# Schaltplan.net
KiCad netlist of a schematic drawn in EAGLE
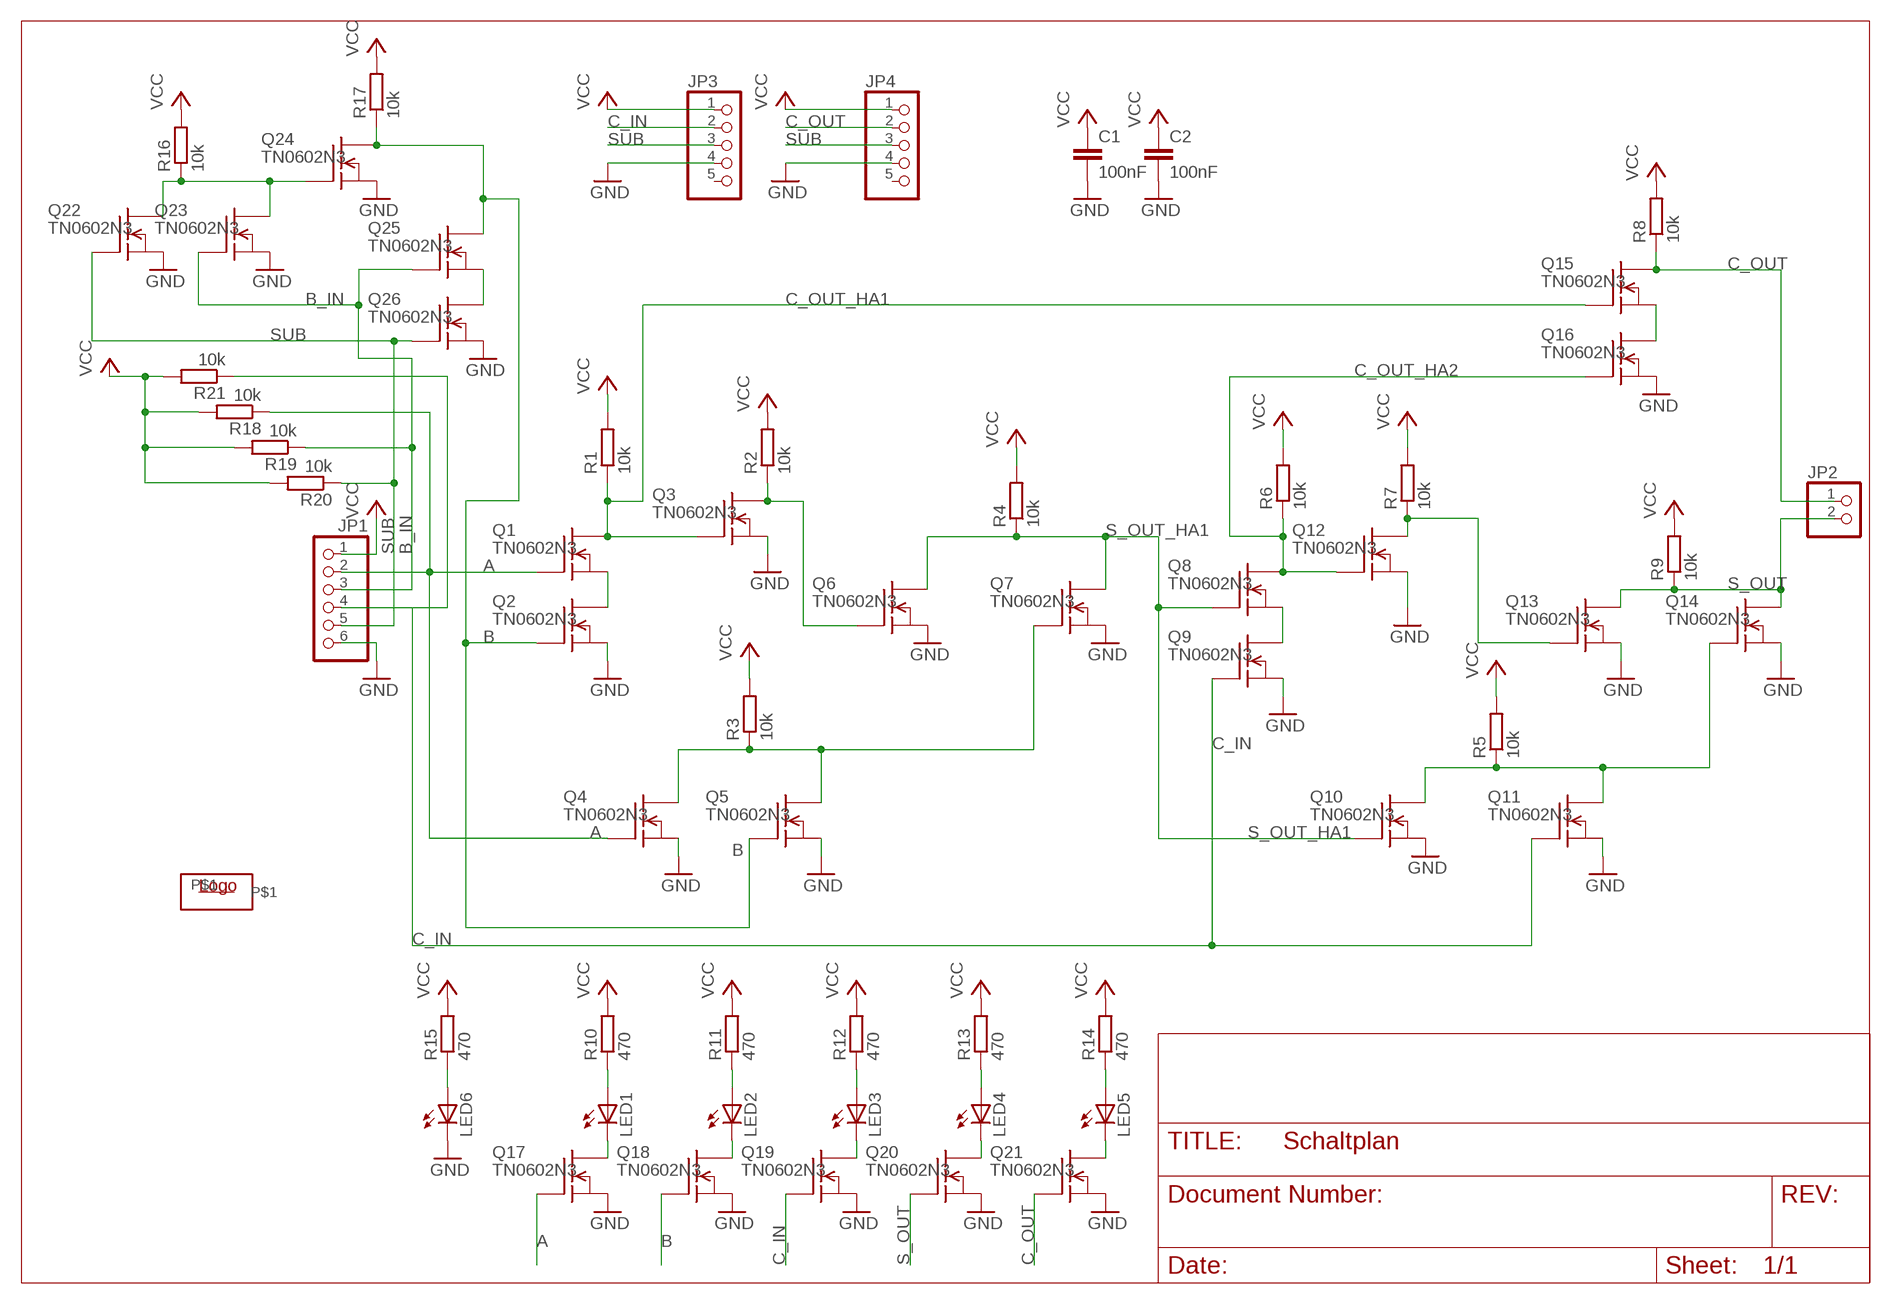
[diagram p0: schematic, sheet 1]

(export (version "E")
  (design (tool "Eeschema 10.0.6"))
  (components
    (comp (ref "C1")
      (value "100nF")
      (footprint "eagle-import:C025-024X044")
      (libsource (lib "eagle-import") (part "C-EU025-024X044"))
    )
    (comp (ref "C2")
      (value "100nF")
      (footprint "eagle-import:C025-024X044")
      (libsource (lib "eagle-import") (part "C-EU025-024X044"))
    )
    (comp (ref "JP1")
      (value "PINHD-1X6")
      (footprint "eagle-import:1X06")
      (libsource (lib "eagle-import") (part "PINHD-1X6"))
    )
    (comp (ref "JP2")
      (value "PINHD-1X2")
      (footprint "eagle-import:1X02")
      (libsource (lib "eagle-import") (part "PINHD-1X2"))
    )
    (comp (ref "JP3")
      (value "PINHD-1X5")
      (footprint "eagle-import:1X05")
      (libsource (lib "eagle-import") (part "PINHD-1X5"))
    )
    (comp (ref "JP4")
      (value "PINHD-1X5")
      (footprint "eagle-import:1X05")
      (libsource (lib "eagle-import") (part "PINHD-1X5"))
    )
    (comp (ref "LED1")
      (value "LED3MM")
      (footprint "eagle-import:LED3MM")
      (libsource (lib "eagle-import") (part "LED3MM"))
    )
    (comp (ref "LED2")
      (value "LED3MM")
      (footprint "eagle-import:LED3MM")
      (libsource (lib "eagle-import") (part "LED3MM"))
    )
    (comp (ref "LED3")
      (value "LED3MM")
      (footprint "eagle-import:LED3MM")
      (libsource (lib "eagle-import") (part "LED3MM"))
    )
    (comp (ref "LED4")
      (value "LED3MM")
      (footprint "eagle-import:LED3MM")
      (libsource (lib "eagle-import") (part "LED3MM"))
    )
    (comp (ref "LED5")
      (value "LED3MM")
      (footprint "eagle-import:LED3MM")
      (libsource (lib "eagle-import") (part "LED3MM"))
    )
    (comp (ref "LED6")
      (value "LED3MM")
      (footprint "eagle-import:LED3MM")
      (libsource (lib "eagle-import") (part "LED3MM"))
    )
    (comp (ref "Q1")
      (value "TN0602N3")
      (footprint "eagle-import:TO-92")
      (libsource (lib "eagle-import") (part "TN0602N3"))
    )
    (comp (ref "Q2")
      (value "TN0602N3")
      (footprint "eagle-import:TO-92")
      (libsource (lib "eagle-import") (part "TN0602N3"))
    )
    (comp (ref "Q3")
      (value "TN0602N3")
      (footprint "eagle-import:TO-92")
      (libsource (lib "eagle-import") (part "TN0602N3"))
    )
    (comp (ref "Q4")
      (value "TN0602N3")
      (footprint "eagle-import:TO-92")
      (libsource (lib "eagle-import") (part "TN0602N3"))
    )
    (comp (ref "Q5")
      (value "TN0602N3")
      (footprint "eagle-import:TO-92")
      (libsource (lib "eagle-import") (part "TN0602N3"))
    )
    (comp (ref "Q6")
      (value "TN0602N3")
      (footprint "eagle-import:TO-92")
      (libsource (lib "eagle-import") (part "TN0602N3"))
    )
    (comp (ref "Q7")
      (value "TN0602N3")
      (footprint "eagle-import:TO-92")
      (libsource (lib "eagle-import") (part "TN0602N3"))
    )
    (comp (ref "Q8")
      (value "TN0602N3")
      (footprint "eagle-import:TO-92")
      (libsource (lib "eagle-import") (part "TN0602N3"))
    )
    (comp (ref "Q9")
      (value "TN0602N3")
      (footprint "eagle-import:TO-92")
      (libsource (lib "eagle-import") (part "TN0602N3"))
    )
    (comp (ref "Q10")
      (value "TN0602N3")
      (footprint "eagle-import:TO-92")
      (libsource (lib "eagle-import") (part "TN0602N3"))
    )
    (comp (ref "Q11")
      (value "TN0602N3")
      (footprint "eagle-import:TO-92")
      (libsource (lib "eagle-import") (part "TN0602N3"))
    )
    (comp (ref "Q12")
      (value "TN0602N3")
      (footprint "eagle-import:TO-92")
      (libsource (lib "eagle-import") (part "TN0602N3"))
    )
    (comp (ref "Q13")
      (value "TN0602N3")
      (footprint "eagle-import:TO-92")
      (libsource (lib "eagle-import") (part "TN0602N3"))
    )
    (comp (ref "Q14")
      (value "TN0602N3")
      (footprint "eagle-import:TO-92")
      (libsource (lib "eagle-import") (part "TN0602N3"))
    )
    (comp (ref "Q15")
      (value "TN0602N3")
      (footprint "eagle-import:TO-92")
      (libsource (lib "eagle-import") (part "TN0602N3"))
    )
    (comp (ref "Q16")
      (value "TN0602N3")
      (footprint "eagle-import:TO-92")
      (libsource (lib "eagle-import") (part "TN0602N3"))
    )
    (comp (ref "Q17")
      (value "TN0602N3")
      (footprint "eagle-import:TO-92")
      (libsource (lib "eagle-import") (part "TN0602N3"))
    )
    (comp (ref "Q18")
      (value "TN0602N3")
      (footprint "eagle-import:TO-92")
      (libsource (lib "eagle-import") (part "TN0602N3"))
    )
    (comp (ref "Q19")
      (value "TN0602N3")
      (footprint "eagle-import:TO-92")
      (libsource (lib "eagle-import") (part "TN0602N3"))
    )
    (comp (ref "Q20")
      (value "TN0602N3")
      (footprint "eagle-import:TO-92")
      (libsource (lib "eagle-import") (part "TN0602N3"))
    )
    (comp (ref "Q21")
      (value "TN0602N3")
      (footprint "eagle-import:TO-92")
      (libsource (lib "eagle-import") (part "TN0602N3"))
    )
    (comp (ref "Q22")
      (value "TN0602N3")
      (footprint "eagle-import:TO-92")
      (libsource (lib "eagle-import") (part "TN0602N3"))
    )
    (comp (ref "Q23")
      (value "TN0602N3")
      (footprint "eagle-import:TO-92")
      (libsource (lib "eagle-import") (part "TN0602N3"))
    )
    (comp (ref "Q24")
      (value "TN0602N3")
      (footprint "eagle-import:TO-92")
      (libsource (lib "eagle-import") (part "TN0602N3"))
    )
    (comp (ref "Q25")
      (value "TN0602N3")
      (footprint "eagle-import:TO-92")
      (libsource (lib "eagle-import") (part "TN0602N3"))
    )
    (comp (ref "Q26")
      (value "TN0602N3")
      (footprint "eagle-import:TO-92")
      (libsource (lib "eagle-import") (part "TN0602N3"))
    )
    (comp (ref "R1")
      (value "10k")
      (footprint "eagle-import:0204V")
      (libsource (lib "eagle-import") (part "R-EU_0204/2V"))
    )
    (comp (ref "R2")
      (value "10k")
      (footprint "eagle-import:0204V")
      (libsource (lib "eagle-import") (part "R-EU_0204/2V"))
    )
    (comp (ref "R3")
      (value "10k")
      (footprint "eagle-import:0204V")
      (libsource (lib "eagle-import") (part "R-EU_0204/2V"))
    )
    (comp (ref "R4")
      (value "10k")
      (footprint "eagle-import:0204V")
      (libsource (lib "eagle-import") (part "R-EU_0204/2V"))
    )
    (comp (ref "R5")
      (value "10k")
      (footprint "eagle-import:0204V")
      (libsource (lib "eagle-import") (part "R-EU_0204/2V"))
    )
    (comp (ref "R6")
      (value "10k")
      (footprint "eagle-import:0204V")
      (libsource (lib "eagle-import") (part "R-EU_0204/2V"))
    )
    (comp (ref "R7")
      (value "10k")
      (footprint "eagle-import:0204V")
      (libsource (lib "eagle-import") (part "R-EU_0204/2V"))
    )
    (comp (ref "R8")
      (value "10k")
      (footprint "eagle-import:0204V")
      (libsource (lib "eagle-import") (part "R-EU_0204/2V"))
    )
    (comp (ref "R9")
      (value "10k")
      (footprint "eagle-import:0204V")
      (libsource (lib "eagle-import") (part "R-EU_0204/2V"))
    )
    (comp (ref "R10")
      (value "470")
      (footprint "eagle-import:0204V")
      (libsource (lib "eagle-import") (part "R-EU_0204/2V"))
    )
    (comp (ref "R11")
      (value "470")
      (footprint "eagle-import:0204V")
      (libsource (lib "eagle-import") (part "R-EU_0204/2V"))
    )
    (comp (ref "R12")
      (value "470")
      (footprint "eagle-import:0204V")
      (libsource (lib "eagle-import") (part "R-EU_0204/2V"))
    )
    (comp (ref "R13")
      (value "470")
      (footprint "eagle-import:0204V")
      (libsource (lib "eagle-import") (part "R-EU_0204/2V"))
    )
    (comp (ref "R14")
      (value "470")
      (footprint "eagle-import:0204V")
      (libsource (lib "eagle-import") (part "R-EU_0204/2V"))
    )
    (comp (ref "R15")
      (value "470")
      (footprint "eagle-import:0204V")
      (libsource (lib "eagle-import") (part "R-EU_0204/2V"))
    )
    (comp (ref "R16")
      (value "10k")
      (footprint "eagle-import:0204V")
      (libsource (lib "eagle-import") (part "R-EU_0204/2V"))
    )
    (comp (ref "R17")
      (value "10k")
      (footprint "eagle-import:0204V")
      (libsource (lib "eagle-import") (part "R-EU_0204/2V"))
    )
    (comp (ref "R18")
      (value "10k")
      (footprint "eagle-import:M0805")
      (libsource (lib "eagle-import") (part "R-EU_M0805"))
    )
    (comp (ref "R19")
      (value "10k")
      (footprint "eagle-import:M0805")
      (libsource (lib "eagle-import") (part "R-EU_M0805"))
    )
    (comp (ref "R20")
      (value "10k")
      (footprint "eagle-import:M0805")
      (libsource (lib "eagle-import") (part "R-EU_M0805"))
    )
    (comp (ref "R21")
      (value "10k")
      (footprint "eagle-import:M0805")
      (libsource (lib "eagle-import") (part "R-EU_M0805"))
    )
    (comp (ref "U$3")
      (value "LOGO")
      (footprint "eagle-import:LOGO")
      (libsource (lib "eagle-import") (part "LOGO"))
    )
  )
  (nets
    (net (code "1") (name "/A") (class "Default")
      (node (ref "JP1") (pin "2") (pinfunction "2_2") (pintype "passive"))
      (node (ref "Q1") (pin "2") (pinfunction "G_2") (pintype "passive"))
      (node (ref "Q17") (pin "2") (pinfunction "G_2") (pintype "passive"))
      (node (ref "Q4") (pin "2") (pinfunction "G_2") (pintype "passive"))
      (node (ref "R18") (pin "1") (pinfunction "1_1") (pintype "passive"))
    )
    (net (code "2") (name "/B") (class "Default")
      (node (ref "Q18") (pin "2") (pinfunction "G_2") (pintype "passive"))
      (node (ref "Q2") (pin "2") (pinfunction "G_2") (pintype "passive"))
      (node (ref "Q24") (pin "3") (pinfunction "D_3") (pintype "passive"))
      (node (ref "Q25") (pin "3") (pinfunction "D_3") (pintype "passive"))
      (node (ref "Q5") (pin "2") (pinfunction "G_2") (pintype "passive"))
      (node (ref "R17") (pin "1") (pinfunction "1_1") (pintype "passive"))
    )
    (net (code "3") (name "/B_IN") (class "Default")
      (node (ref "JP1") (pin "3") (pinfunction "3_3") (pintype "passive"))
      (node (ref "Q23") (pin "2") (pinfunction "G_2") (pintype "passive"))
      (node (ref "Q25") (pin "2") (pinfunction "G_2") (pintype "passive"))
      (node (ref "R19") (pin "1") (pinfunction "1_1") (pintype "passive"))
    )
    (net (code "4") (name "/C_IN") (class "Default")
      (node (ref "JP1") (pin "4") (pinfunction "4_4") (pintype "passive"))
      (node (ref "JP3") (pin "2") (pinfunction "2_2") (pintype "passive"))
      (node (ref "Q11") (pin "2") (pinfunction "G_2") (pintype "passive"))
      (node (ref "Q19") (pin "2") (pinfunction "G_2") (pintype "passive"))
      (node (ref "Q9") (pin "2") (pinfunction "G_2") (pintype "passive"))
      (node (ref "R21") (pin "1") (pinfunction "1_1") (pintype "passive"))
    )
    (net (code "5") (name "/C_OUT") (class "Default")
      (node (ref "JP2") (pin "1") (pinfunction "1_1") (pintype "passive"))
      (node (ref "JP4") (pin "2") (pinfunction "2_2") (pintype "passive"))
      (node (ref "Q15") (pin "3") (pinfunction "D_3") (pintype "passive"))
      (node (ref "Q21") (pin "2") (pinfunction "G_2") (pintype "passive"))
      (node (ref "R8") (pin "1") (pinfunction "1_1") (pintype "passive"))
    )
    (net (code "6") (name "/C_OUT_HA1") (class "Default")
      (node (ref "Q1") (pin "3") (pinfunction "D_3") (pintype "passive"))
      (node (ref "Q15") (pin "2") (pinfunction "G_2") (pintype "passive"))
      (node (ref "Q3") (pin "2") (pinfunction "G_2") (pintype "passive"))
      (node (ref "R1") (pin "1") (pinfunction "1_1") (pintype "passive"))
    )
    (net (code "7") (name "/C_OUT_HA2") (class "Default")
      (node (ref "Q12") (pin "2") (pinfunction "G_2") (pintype "passive"))
      (node (ref "Q16") (pin "2") (pinfunction "G_2") (pintype "passive"))
      (node (ref "Q8") (pin "3") (pinfunction "D_3") (pintype "passive"))
      (node (ref "R6") (pin "1") (pinfunction "1_1") (pintype "passive"))
    )
    (net (code "8") (name "/SUB") (class "Default")
      (node (ref "JP1") (pin "5") (pinfunction "5_5") (pintype "passive"))
      (node (ref "JP3") (pin "3") (pinfunction "3_3") (pintype "passive"))
      (node (ref "JP4") (pin "3") (pinfunction "3_3") (pintype "passive"))
      (node (ref "Q22") (pin "2") (pinfunction "G_2") (pintype "passive"))
      (node (ref "Q26") (pin "2") (pinfunction "G_2") (pintype "passive"))
      (node (ref "R20") (pin "1") (pinfunction "1_1") (pintype "passive"))
    )
    (net (code "9") (name "/S_OUT") (class "Default")
      (node (ref "JP2") (pin "2") (pinfunction "2_2") (pintype "passive"))
      (node (ref "Q13") (pin "3") (pinfunction "D_3") (pintype "passive"))
      (node (ref "Q14") (pin "3") (pinfunction "D_3") (pintype "passive"))
      (node (ref "Q20") (pin "2") (pinfunction "G_2") (pintype "passive"))
      (node (ref "R9") (pin "1") (pinfunction "1_1") (pintype "passive"))
    )
    (net (code "10") (name "/S_OUT_HA1") (class "Default")
      (node (ref "Q10") (pin "2") (pinfunction "G_2") (pintype "passive"))
      (node (ref "Q6") (pin "3") (pinfunction "D_3") (pintype "passive"))
      (node (ref "Q7") (pin "3") (pinfunction "D_3") (pintype "passive"))
      (node (ref "Q8") (pin "2") (pinfunction "G_2") (pintype "passive"))
      (node (ref "R4") (pin "1") (pinfunction "1_1") (pintype "passive"))
    )
    (net (code "11") (name "GND") (class "Default")
      (node (ref "C1") (pin "2") (pinfunction "2_2") (pintype "passive"))
      (node (ref "C2") (pin "2") (pinfunction "2_2") (pintype "passive"))
      (node (ref "JP1") (pin "6") (pinfunction "6_6") (pintype "passive"))
      (node (ref "JP3") (pin "4") (pinfunction "4_4") (pintype "passive"))
      (node (ref "JP4") (pin "4") (pinfunction "4_4") (pintype "passive"))
      (node (ref "LED6") (pin "K") (pinfunction "C_K") (pintype "passive"))
      (node (ref "Q10") (pin "1") (pinfunction "S_1") (pintype "passive"))
      (node (ref "Q11") (pin "1") (pinfunction "S_1") (pintype "passive"))
      (node (ref "Q12") (pin "1") (pinfunction "S_1") (pintype "passive"))
      (node (ref "Q13") (pin "1") (pinfunction "S_1") (pintype "passive"))
      (node (ref "Q14") (pin "1") (pinfunction "S_1") (pintype "passive"))
      (node (ref "Q16") (pin "1") (pinfunction "S_1") (pintype "passive"))
      (node (ref "Q17") (pin "1") (pinfunction "S_1") (pintype "passive"))
      (node (ref "Q18") (pin "1") (pinfunction "S_1") (pintype "passive"))
      (node (ref "Q19") (pin "1") (pinfunction "S_1") (pintype "passive"))
      (node (ref "Q2") (pin "1") (pinfunction "S_1") (pintype "passive"))
      (node (ref "Q20") (pin "1") (pinfunction "S_1") (pintype "passive"))
      (node (ref "Q21") (pin "1") (pinfunction "S_1") (pintype "passive"))
      (node (ref "Q22") (pin "1") (pinfunction "S_1") (pintype "passive"))
      (node (ref "Q23") (pin "1") (pinfunction "S_1") (pintype "passive"))
      (node (ref "Q24") (pin "1") (pinfunction "S_1") (pintype "passive"))
      (node (ref "Q26") (pin "1") (pinfunction "S_1") (pintype "passive"))
      (node (ref "Q3") (pin "1") (pinfunction "S_1") (pintype "passive"))
      (node (ref "Q4") (pin "1") (pinfunction "S_1") (pintype "passive"))
      (node (ref "Q5") (pin "1") (pinfunction "S_1") (pintype "passive"))
      (node (ref "Q6") (pin "1") (pinfunction "S_1") (pintype "passive"))
      (node (ref "Q7") (pin "1") (pinfunction "S_1") (pintype "passive"))
      (node (ref "Q9") (pin "1") (pinfunction "S_1") (pintype "passive"))
    )
    (net (code "12") (name "Net-(LED1-C)") (class "Default")
      (node (ref "LED1") (pin "K") (pinfunction "C_K") (pintype "passive"))
      (node (ref "Q17") (pin "3") (pinfunction "D_3") (pintype "passive"))
    )
    (net (code "13") (name "Net-(LED1-PadA)") (class "Default")
      (node (ref "LED1") (pin "A") (pinfunction "A_A") (pintype "passive"))
      (node (ref "R10") (pin "1") (pinfunction "1_1") (pintype "passive"))
    )
    (net (code "14") (name "Net-(LED2-C)") (class "Default")
      (node (ref "LED2") (pin "K") (pinfunction "C_K") (pintype "passive"))
      (node (ref "Q18") (pin "3") (pinfunction "D_3") (pintype "passive"))
    )
    (net (code "15") (name "Net-(LED2-PadA)") (class "Default")
      (node (ref "LED2") (pin "A") (pinfunction "A_A") (pintype "passive"))
      (node (ref "R11") (pin "1") (pinfunction "1_1") (pintype "passive"))
    )
    (net (code "16") (name "Net-(LED3-C)") (class "Default")
      (node (ref "LED3") (pin "K") (pinfunction "C_K") (pintype "passive"))
      (node (ref "Q19") (pin "3") (pinfunction "D_3") (pintype "passive"))
    )
    (net (code "17") (name "Net-(LED3-PadA)") (class "Default")
      (node (ref "LED3") (pin "A") (pinfunction "A_A") (pintype "passive"))
      (node (ref "R12") (pin "1") (pinfunction "1_1") (pintype "passive"))
    )
    (net (code "18") (name "Net-(LED4-C)") (class "Default")
      (node (ref "LED4") (pin "K") (pinfunction "C_K") (pintype "passive"))
      (node (ref "Q20") (pin "3") (pinfunction "D_3") (pintype "passive"))
    )
    (net (code "19") (name "Net-(LED4-PadA)") (class "Default")
      (node (ref "LED4") (pin "A") (pinfunction "A_A") (pintype "passive"))
      (node (ref "R13") (pin "1") (pinfunction "1_1") (pintype "passive"))
    )
    (net (code "20") (name "Net-(LED5-C)") (class "Default")
      (node (ref "LED5") (pin "K") (pinfunction "C_K") (pintype "passive"))
      (node (ref "Q21") (pin "3") (pinfunction "D_3") (pintype "passive"))
    )
    (net (code "21") (name "Net-(LED5-PadA)") (class "Default")
      (node (ref "LED5") (pin "A") (pinfunction "A_A") (pintype "passive"))
      (node (ref "R14") (pin "1") (pinfunction "1_1") (pintype "passive"))
    )
    (net (code "22") (name "Net-(LED6-PadA)") (class "Default")
      (node (ref "LED6") (pin "A") (pinfunction "A_A") (pintype "passive"))
      (node (ref "R15") (pin "1") (pinfunction "1_1") (pintype "passive"))
    )
    (net (code "23") (name "Net-(Q1-S)") (class "Default")
      (node (ref "Q1") (pin "1") (pinfunction "S_1") (pintype "passive"))
      (node (ref "Q2") (pin "3") (pinfunction "D_3") (pintype "passive"))
    )
    (net (code "24") (name "Net-(Q3-D)") (class "Default")
      (node (ref "Q3") (pin "3") (pinfunction "D_3") (pintype "passive"))
      (node (ref "Q6") (pin "2") (pinfunction "G_2") (pintype "passive"))
      (node (ref "R2") (pin "1") (pinfunction "1_1") (pintype "passive"))
    )
    (net (code "25") (name "Net-(Q4-D)") (class "Default")
      (node (ref "Q4") (pin "3") (pinfunction "D_3") (pintype "passive"))
      (node (ref "Q5") (pin "3") (pinfunction "D_3") (pintype "passive"))
      (node (ref "Q7") (pin "2") (pinfunction "G_2") (pintype "passive"))
      (node (ref "R3") (pin "1") (pinfunction "1_1") (pintype "passive"))
    )
    (net (code "26") (name "Net-(Q8-S)") (class "Default")
      (node (ref "Q8") (pin "1") (pinfunction "S_1") (pintype "passive"))
      (node (ref "Q9") (pin "3") (pinfunction "D_3") (pintype "passive"))
    )
    (net (code "27") (name "Net-(Q10-D)") (class "Default")
      (node (ref "Q10") (pin "3") (pinfunction "D_3") (pintype "passive"))
      (node (ref "Q11") (pin "3") (pinfunction "D_3") (pintype "passive"))
      (node (ref "Q14") (pin "2") (pinfunction "G_2") (pintype "passive"))
      (node (ref "R5") (pin "1") (pinfunction "1_1") (pintype "passive"))
    )
    (net (code "28") (name "Net-(Q12-D)") (class "Default")
      (node (ref "Q12") (pin "3") (pinfunction "D_3") (pintype "passive"))
      (node (ref "Q13") (pin "2") (pinfunction "G_2") (pintype "passive"))
      (node (ref "R7") (pin "1") (pinfunction "1_1") (pintype "passive"))
    )
    (net (code "29") (name "Net-(Q15-S)") (class "Default")
      (node (ref "Q15") (pin "1") (pinfunction "S_1") (pintype "passive"))
      (node (ref "Q16") (pin "3") (pinfunction "D_3") (pintype "passive"))
    )
    (net (code "30") (name "Net-(Q22-D)") (class "Default")
      (node (ref "Q22") (pin "3") (pinfunction "D_3") (pintype "passive"))
      (node (ref "Q23") (pin "3") (pinfunction "D_3") (pintype "passive"))
      (node (ref "Q24") (pin "2") (pinfunction "G_2") (pintype "passive"))
      (node (ref "R16") (pin "1") (pinfunction "1_1") (pintype "passive"))
    )
    (net (code "31") (name "Net-(Q25-S)") (class "Default")
      (node (ref "Q25") (pin "1") (pinfunction "S_1") (pintype "passive"))
      (node (ref "Q26") (pin "3") (pinfunction "D_3") (pintype "passive"))
    )
    (net (code "32") (name "VCC") (class "Default")
      (node (ref "C1") (pin "1") (pinfunction "1_1") (pintype "passive"))
      (node (ref "C2") (pin "1") (pinfunction "1_1") (pintype "passive"))
      (node (ref "JP1") (pin "1") (pinfunction "1_1") (pintype "passive"))
      (node (ref "JP3") (pin "1") (pinfunction "1_1") (pintype "passive"))
      (node (ref "JP4") (pin "1") (pinfunction "1_1") (pintype "passive"))
      (node (ref "R1") (pin "2") (pinfunction "2_2") (pintype "passive"))
      (node (ref "R10") (pin "2") (pinfunction "2_2") (pintype "passive"))
      (node (ref "R11") (pin "2") (pinfunction "2_2") (pintype "passive"))
      (node (ref "R12") (pin "2") (pinfunction "2_2") (pintype "passive"))
      (node (ref "R13") (pin "2") (pinfunction "2_2") (pintype "passive"))
      (node (ref "R14") (pin "2") (pinfunction "2_2") (pintype "passive"))
      (node (ref "R15") (pin "2") (pinfunction "2_2") (pintype "passive"))
      (node (ref "R16") (pin "2") (pinfunction "2_2") (pintype "passive"))
      (node (ref "R17") (pin "2") (pinfunction "2_2") (pintype "passive"))
      (node (ref "R18") (pin "2") (pinfunction "2_2") (pintype "passive"))
      (node (ref "R19") (pin "2") (pinfunction "2_2") (pintype "passive"))
      (node (ref "R2") (pin "2") (pinfunction "2_2") (pintype "passive"))
      (node (ref "R20") (pin "2") (pinfunction "2_2") (pintype "passive"))
      (node (ref "R21") (pin "2") (pinfunction "2_2") (pintype "passive"))
      (node (ref "R3") (pin "2") (pinfunction "2_2") (pintype "passive"))
      (node (ref "R4") (pin "2") (pinfunction "2_2") (pintype "passive"))
      (node (ref "R5") (pin "2") (pinfunction "2_2") (pintype "passive"))
      (node (ref "R6") (pin "2") (pinfunction "2_2") (pintype "passive"))
      (node (ref "R7") (pin "2") (pinfunction "2_2") (pintype "passive"))
      (node (ref "R8") (pin "2") (pinfunction "2_2") (pintype "passive"))
      (node (ref "R9") (pin "2") (pinfunction "2_2") (pintype "passive"))
    )
    (net (code "33") (name "unconnected-(JP3-Pad5)") (class "Default")
      (node (ref "JP3") (pin "5") (pinfunction "5_5") (pintype "passive"))
    )
    (net (code "34") (name "unconnected-(JP4-Pad5)") (class "Default")
      (node (ref "JP4") (pin "5") (pinfunction "5_5") (pintype "passive"))
    )
    (net (code "35") (name "unconnected-(U$3-PadP$1)") (class "Default")
      (node (ref "U$3") (pin "P$1") (pinfunction "P$1_P$1") (pintype "bidirectional"))
    )
  )
)
